# 5VRegulator.net
KiCad netlist of a schematic drawn in Altium Designer
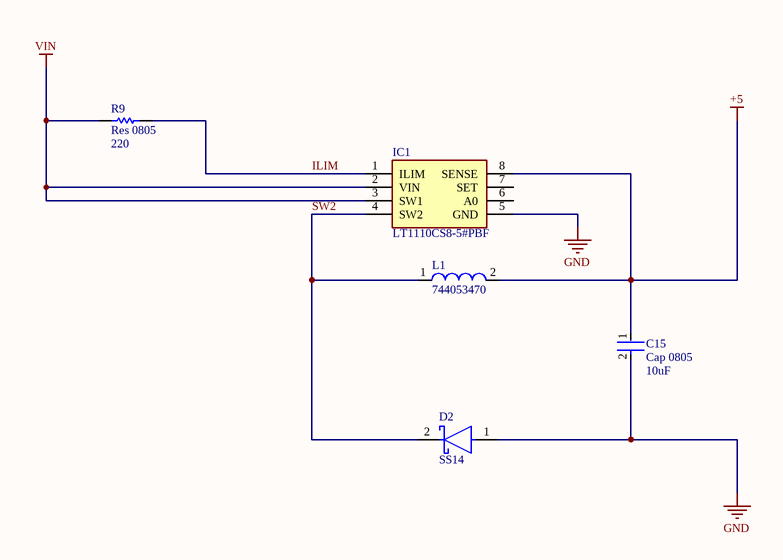
[diagram p0: 5VRegulator.SchDoc]

(export (version "E")
  (design (tool "Eeschema 10.0.6"))
  (components
    (comp (ref "C15")
      (value "Cap 0805")
      (footprint "FP-GRM216-0_1-IPC_C")
      (description "Capacitor")
      (fields (field (name "ALTIUM_VALUE") "10uF"))
      (libsource (lib "Altium Content Vault") (part "236180d848d6139a670b325ea6854c9"))
    )
    (comp (ref "D2")
      (value "SS14")
      (footprint "FP-403AE-MFG")
      (description "DIODE SCHOTTKY 40V 1A SMA")
      (fields
        (field (name "MANUFACTURER") "ON Semiconductor")
        (field (name "OCTOPART") "https://octopart.com/ss14-on+semiconductor-29205033")
      )
      (libsource (lib "Altium Content Vault") (part "360ad2f4ac25a952324d13796385471"))
    )
    (comp (ref "IC1")
      (value "LT1110CS8-5#PBF")
      (footprint "SamacSys:SOIC127P599X175-8N")
      (description "Conv DC-DC 1V to 30V Non-Inv/Inv/Step Up/Step Down Single-Out 5V Micropower 8-Pin SOIC N Tube")
      (fields (field (name "MOUSER PART NUMBER") "584-LT1110CS8-5#PBF"))
      (libsource (lib "*") (part "LT1110CS8#PBF"))
    )
    (comp (ref "L1")
      (value "744053470")
      (footprint "WE-TPC-5828-LH")
      (description "SMD Shielded Tiny Power Inductor WE-TPC, L = 47.0 µH")
      (libsource (lib "Altium Content Vault") (part "PAS-IND-INDUCTOR-2"))
    )
    (comp (ref "R9")
      (value "Res 0805")
      (footprint "RESC2013X50X30LL20T20")
      (description "Resistor")
      (fields (field (name "ALTIUM_VALUE") "220"))
      (libsource (lib "Altium Content Vault") (part "RES"))
    )
  )
  (nets
    (net (code "1") (name "+5") (class "Default")
      (node (ref "C15") (pin "1") (pinfunction "1_1") (pintype "passive"))
      (node (ref "IC1") (pin "8") (pinfunction "SENSE_8") (pintype "passive"))
      (node (ref "L1") (pin "2") (pinfunction "2_2") (pintype "passive"))
    )
    (net (code "2") (name "/ILIM") (class "Default")
      (node (ref "IC1") (pin "1") (pinfunction "ILIM_1") (pintype "passive"))
      (node (ref "R9") (pin "1") (pinfunction "1_1") (pintype "passive"))
    )
    (net (code "3") (name "/SW2") (class "Default")
      (node (ref "D2") (pin "2") (pinfunction "C_2") (pintype "passive"))
      (node (ref "IC1") (pin "4") (pinfunction "SW2_4") (pintype "passive"))
      (node (ref "L1") (pin "1") (pinfunction "1_1") (pintype "passive"))
    )
    (net (code "4") (name "GND") (class "Default")
      (node (ref "C15") (pin "2") (pinfunction "2_2") (pintype "passive"))
      (node (ref "D2") (pin "1") (pinfunction "A_1") (pintype "passive"))
      (node (ref "IC1") (pin "5") (pinfunction "GND_5") (pintype "passive"))
    )
    (net (code "5") (name "VIN") (class "Default")
      (node (ref "IC1") (pin "2") (pinfunction "VIN_2") (pintype "passive"))
      (node (ref "IC1") (pin "3") (pinfunction "SW1_3") (pintype "passive"))
      (node (ref "R9") (pin "2") (pinfunction "2_2") (pintype "passive"))
    )
    (net (code "6") (name "unconnected-(IC1-A0-Pad6)") (class "Default")
      (node (ref "IC1") (pin "6") (pinfunction "A0_6") (pintype "passive"))
    )
    (net (code "7") (name "unconnected-(IC1-SET-Pad7)") (class "Default")
      (node (ref "IC1") (pin "7") (pinfunction "SET_7") (pintype "passive"))
    )
  )
)
